# POE_RS-485.net
KiCad netlist of a schematic drawn in EAGLE
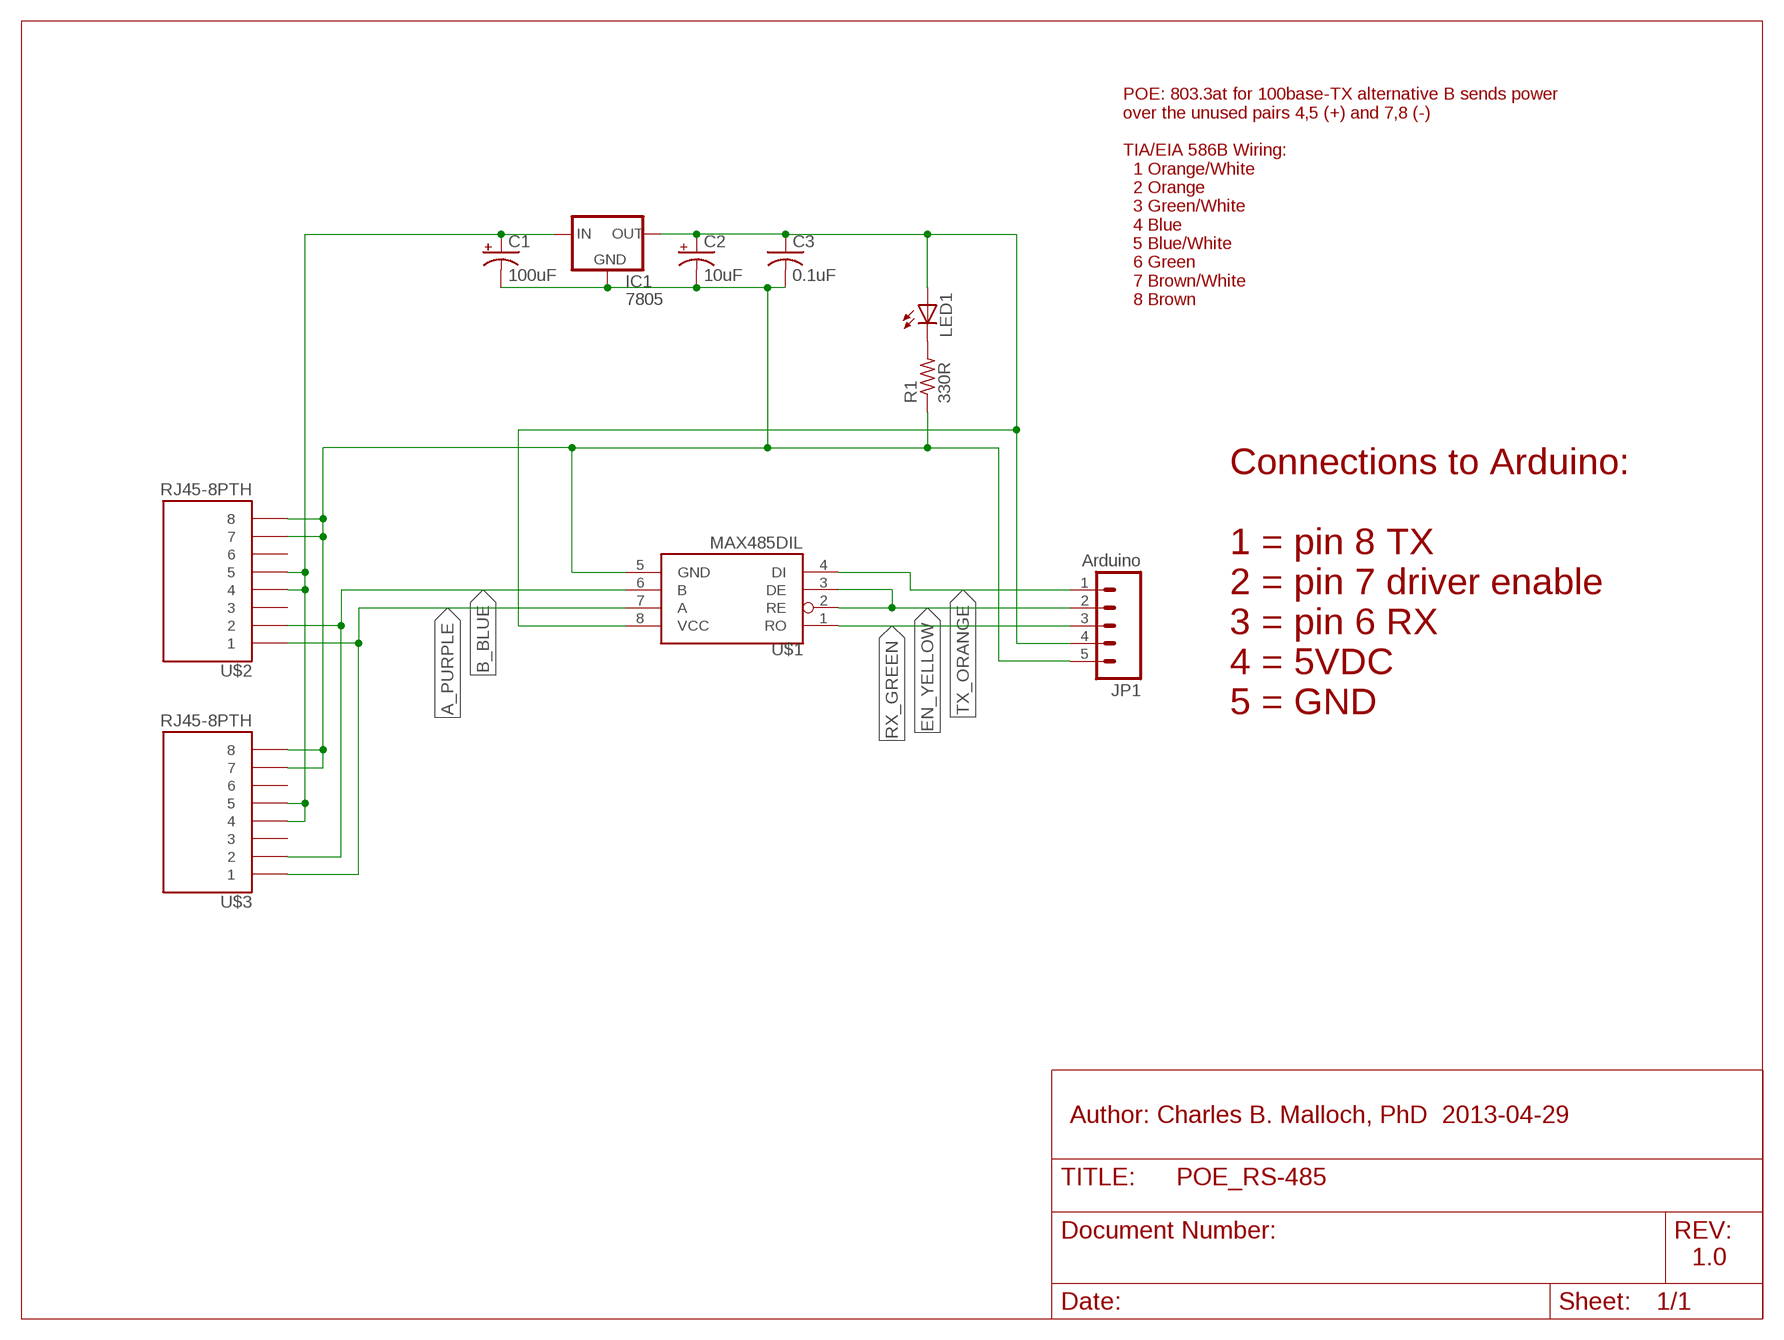
[diagram p0: schematic, sheet 1]

(export (version "E")
  (design (tool "Eeschema 10.0.6"))
  (components
    (comp (ref "C1")
      (value "100uF")
      (footprint "eagle-import:TT2D7")
      (libsource (lib "eagle-import") (part "CPOL-USTT2D7"))
    )
    (comp (ref "C2")
      (value "10uF")
      (footprint "eagle-import:E1,8-4")
      (libsource (lib "eagle-import") (part "CPOL-USE1.8-4"))
    )
    (comp (ref "C3")
      (value "0.1uF")
      (footprint "eagle-import:C025-025X050")
      (libsource (lib "eagle-import") (part "C-US025-025X050"))
    )
    (comp (ref "IC1")
      (value "7805")
      (footprint "eagle-import:TO-220-ALT")
      (libsource (lib "eagle-import") (part "V_REG_78XX-TO-220"))
    )
    (comp (ref "JP1")
      (value "Arduino")
      (footprint "eagle-import:1X05_LOCK_LONGPADS")
      (libsource (lib "eagle-import") (part "M05LOCK_LONGPADS"))
    )
    (comp (ref "LED1")
      (value "LED3MM")
      (footprint "eagle-import:LED3MM")
      (libsource (lib "eagle-import") (part "LED3MM"))
    )
    (comp (ref "R1")
      (value "330R")
      (footprint "eagle-import:0204_7")
      (libsource (lib "eagle-import") (part "R-US_0204/7"))
    )
    (comp (ref "U$1")
      (value "MAX485DIL")
      (footprint "eagle-import:DIL08")
      (libsource (lib "eagle-import") (part "MAX485DIL"))
    )
    (comp (ref "U$2")
      (value "RJ45-8PTH")
      (footprint "eagle-import:RJ45-8")
      (libsource (lib "eagle-import") (part "RJ45-8PTH"))
    )
    (comp (ref "U$3")
      (value "RJ45-8PTH")
      (footprint "eagle-import:RJ45-8")
      (libsource (lib "eagle-import") (part "RJ45-8PTH"))
    )
  )
  (nets
    (net (code "1") (name "A_PURPLE") (class "Default")
      (node (ref "U$1") (pin "7") (pinfunction "A_7") (pintype "bidirectional"))
      (node (ref "U$2") (pin "1") (pinfunction "1_1") (pintype "bidirectional"))
      (node (ref "U$3") (pin "1") (pinfunction "1_1") (pintype "bidirectional"))
    )
    (net (code "2") (name "B_BLUE") (class "Default")
      (node (ref "U$1") (pin "6") (pinfunction "B_6") (pintype "bidirectional"))
      (node (ref "U$2") (pin "2") (pinfunction "2_2") (pintype "bidirectional"))
      (node (ref "U$3") (pin "2") (pinfunction "2_2") (pintype "bidirectional"))
    )
    (net (code "3") (name "EN_YELLOW") (class "Default")
      (node (ref "JP1") (pin "2") (pinfunction "2_2") (pintype "passive"))
      (node (ref "U$1") (pin "2") (pinfunction "RE_2") (pintype "bidirectional"))
      (node (ref "U$1") (pin "3") (pinfunction "DE_3") (pintype "bidirectional"))
    )
    (net (code "4") (name "Net-(C1-Pad+)") (class "Default")
      (node (ref "C1") (pin "+") (pinfunction "+_+") (pintype "passive"))
      (node (ref "IC1") (pin "IN") (pinfunction "IN_IN") (pintype "input"))
      (node (ref "U$2") (pin "4") (pinfunction "4_4") (pintype "bidirectional"))
      (node (ref "U$2") (pin "5") (pinfunction "5_5") (pintype "bidirectional"))
      (node (ref "U$3") (pin "4") (pinfunction "4_4") (pintype "bidirectional"))
      (node (ref "U$3") (pin "5") (pinfunction "5_5") (pintype "bidirectional"))
    )
    (net (code "5") (name "Net-(LED1-C)") (class "Default")
      (node (ref "LED1") (pin "K") (pinfunction "C_K") (pintype "passive"))
      (node (ref "R1") (pin "2") (pinfunction "2_2") (pintype "passive"))
    )
    (net (code "6") (name "Net-(U$1-GND)") (class "Default")
      (node (ref "C1") (pin "-") (pinfunction "-_-") (pintype "passive"))
      (node (ref "C2") (pin "-") (pinfunction "-_-") (pintype "passive"))
      (node (ref "C3") (pin "2") (pinfunction "2_2") (pintype "passive"))
      (node (ref "IC1") (pin "GND") (pinfunction "GND_GND") (pintype "input"))
      (node (ref "JP1") (pin "5") (pinfunction "5_5") (pintype "passive"))
      (node (ref "R1") (pin "1") (pinfunction "1_1") (pintype "passive"))
      (node (ref "U$1") (pin "5") (pinfunction "GND_5") (pintype "bidirectional"))
      (node (ref "U$2") (pin "7") (pinfunction "7_7") (pintype "bidirectional"))
      (node (ref "U$2") (pin "8") (pinfunction "8_8") (pintype "bidirectional"))
      (node (ref "U$3") (pin "7") (pinfunction "7_7") (pintype "bidirectional"))
      (node (ref "U$3") (pin "8") (pinfunction "8_8") (pintype "bidirectional"))
    )
    (net (code "7") (name "Net-(U$1-VCC)") (class "Default")
      (node (ref "C2") (pin "+") (pinfunction "+_+") (pintype "passive"))
      (node (ref "C3") (pin "1") (pinfunction "1_1") (pintype "passive"))
      (node (ref "IC1") (pin "OUT") (pinfunction "OUT_OUT") (pintype "output"))
      (node (ref "JP1") (pin "4") (pinfunction "4_4") (pintype "passive"))
      (node (ref "LED1") (pin "A") (pinfunction "A_A") (pintype "passive"))
      (node (ref "U$1") (pin "8") (pinfunction "VCC_8") (pintype "bidirectional"))
    )
    (net (code "8") (name "RX_GREEN") (class "Default")
      (node (ref "JP1") (pin "3") (pinfunction "3_3") (pintype "passive"))
      (node (ref "U$1") (pin "1") (pinfunction "RO_1") (pintype "bidirectional"))
    )
    (net (code "9") (name "TX_ORANGE") (class "Default")
      (node (ref "JP1") (pin "1") (pinfunction "1_1") (pintype "passive"))
      (node (ref "U$1") (pin "4") (pinfunction "DI_4") (pintype "bidirectional"))
    )
    (net (code "10") (name "unconnected-(U$2-Pad3)") (class "Default")
      (node (ref "U$2") (pin "3") (pinfunction "3_3") (pintype "bidirectional"))
    )
    (net (code "11") (name "unconnected-(U$2-Pad6)") (class "Default")
      (node (ref "U$2") (pin "6") (pinfunction "6_6") (pintype "bidirectional"))
    )
    (net (code "12") (name "unconnected-(U$3-Pad3)") (class "Default")
      (node (ref "U$3") (pin "3") (pinfunction "3_3") (pintype "bidirectional"))
    )
    (net (code "13") (name "unconnected-(U$3-Pad6)") (class "Default")
      (node (ref "U$3") (pin "6") (pinfunction "6_6") (pintype "bidirectional"))
    )
  )
)
